# CoProcessor.net
KiCad netlist of a schematic drawn in Altium Designer
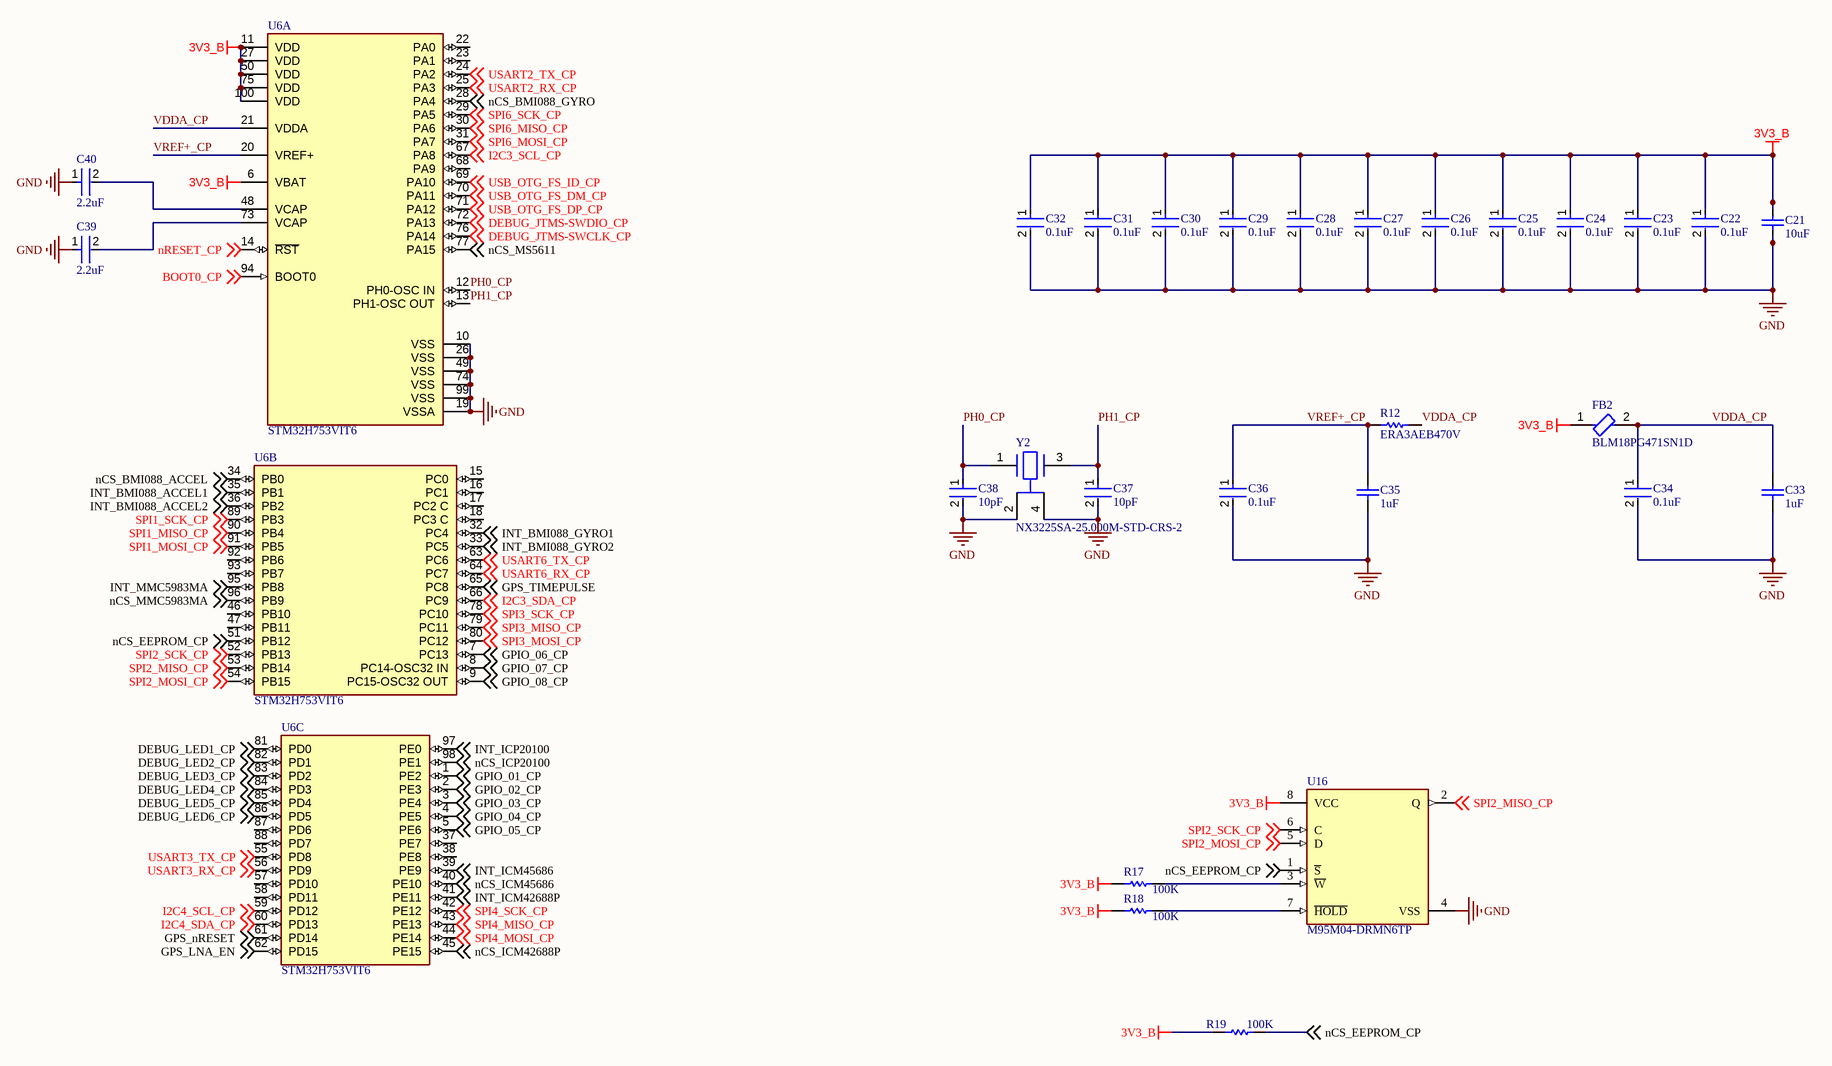
[diagram p0: CoProcessor.SchDoc]

(export (version "E")
  (design (tool "Eeschema 10.0.6"))
  (components
    (comp (ref "C21")
      (value "10uF")
      (footprint "CAPC2013X145X50LL20T25")
      (fields (field (name "MANUFACTURER") "Kemet") (field (name "PART NUMBER") "C0805C106K8RACTU"))
      (libsource (lib "Altium Content Vault") (part "CAP"))
    )
    (comp (ref "C22")
      (value "0.1uF")
      (footprint "FP-C0603C-CF-MFG")
      (description "CAP CER 0.1UF 50V X7R 0603")
      (fields (field (name "TOLERANCE") "0.1") (field (name "MANUFACTURER") "KEMET"))
      (libsource (lib "Altium Content Vault") (part "b4654b650e69147ec39a6b967a45e02"))
    )
    (comp (ref "C23")
      (value "0.1uF")
      (footprint "FP-C0603C-CF-MFG")
      (description "CAP CER 0.1UF 50V X7R 0603")
      (fields (field (name "TOLERANCE") "0.1") (field (name "MANUFACTURER") "KEMET"))
      (libsource (lib "Altium Content Vault") (part "b4654b650e69147ec39a6b967a45e02"))
    )
    (comp (ref "C24")
      (value "0.1uF")
      (footprint "FP-C0603C-CF-MFG")
      (description "CAP CER 0.1UF 50V X7R 0603")
      (fields (field (name "TOLERANCE") "0.1") (field (name "MANUFACTURER") "KEMET"))
      (libsource (lib "Altium Content Vault") (part "b4654b650e69147ec39a6b967a45e02"))
    )
    (comp (ref "C25")
      (value "0.1uF")
      (footprint "FP-C0603C-CF-MFG")
      (description "CAP CER 0.1UF 50V X7R 0603")
      (fields (field (name "TOLERANCE") "0.1") (field (name "MANUFACTURER") "KEMET"))
      (libsource (lib "Altium Content Vault") (part "b4654b650e69147ec39a6b967a45e02"))
    )
    (comp (ref "C26")
      (value "0.1uF")
      (footprint "FP-C0603C-CF-MFG")
      (description "CAP CER 0.1UF 50V X7R 0603")
      (fields (field (name "TOLERANCE") "0.1") (field (name "MANUFACTURER") "KEMET"))
      (libsource (lib "Altium Content Vault") (part "b4654b650e69147ec39a6b967a45e02"))
    )
    (comp (ref "C27")
      (value "0.1uF")
      (footprint "FP-C0603C-CF-MFG")
      (description "CAP CER 0.1UF 50V X7R 0603")
      (fields (field (name "TOLERANCE") "0.1") (field (name "MANUFACTURER") "KEMET"))
      (libsource (lib "Altium Content Vault") (part "b4654b650e69147ec39a6b967a45e02"))
    )
    (comp (ref "C28")
      (value "0.1uF")
      (footprint "FP-C0603C-CF-MFG")
      (description "CAP CER 0.1UF 50V X7R 0603")
      (fields (field (name "TOLERANCE") "0.1") (field (name "MANUFACTURER") "KEMET"))
      (libsource (lib "Altium Content Vault") (part "b4654b650e69147ec39a6b967a45e02"))
    )
    (comp (ref "C29")
      (value "0.1uF")
      (footprint "FP-C0603C-CF-MFG")
      (description "CAP CER 0.1UF 50V X7R 0603")
      (fields (field (name "TOLERANCE") "0.1") (field (name "MANUFACTURER") "KEMET"))
      (libsource (lib "Altium Content Vault") (part "b4654b650e69147ec39a6b967a45e02"))
    )
    (comp (ref "C30")
      (value "0.1uF")
      (footprint "FP-C0603C-CF-MFG")
      (description "CAP CER 0.1UF 50V X7R 0603")
      (fields (field (name "TOLERANCE") "0.1") (field (name "MANUFACTURER") "KEMET"))
      (libsource (lib "Altium Content Vault") (part "b4654b650e69147ec39a6b967a45e02"))
    )
    (comp (ref "C31")
      (value "0.1uF")
      (footprint "FP-C0603C-CF-MFG")
      (description "CAP CER 0.1UF 50V X7R 0603")
      (fields (field (name "TOLERANCE") "0.1") (field (name "MANUFACTURER") "KEMET"))
      (libsource (lib "Altium Content Vault") (part "b4654b650e69147ec39a6b967a45e02"))
    )
    (comp (ref "C32")
      (value "0.1uF")
      (footprint "FP-C0603C-CF-MFG")
      (description "CAP CER 0.1UF 50V X7R 0603")
      (fields (field (name "TOLERANCE") "0.1") (field (name "MANUFACTURER") "KEMET"))
      (libsource (lib "Altium Content Vault") (part "b4654b650e69147ec39a6b967a45e02"))
    )
    (comp (ref "C33")
      (value "1uF")
      (footprint "CAPC1608X90X35LL15T15")
      (fields (field (name "MANUFACTURER") "Kemet") (field (name "PART NUMBER") "C0603C105K4RACTU"))
      (libsource (lib "Altium Content Vault") (part "CAP"))
    )
    (comp (ref "C34")
      (value "0.1uF")
      (footprint "FP-C0603C-CF-MFG")
      (description "CAP CER 0.1UF 50V X7R 0603")
      (fields (field (name "TOLERANCE") "0.1") (field (name "MANUFACTURER") "KEMET"))
      (libsource (lib "Altium Content Vault") (part "b4654b650e69147ec39a6b967a45e02"))
    )
    (comp (ref "C35")
      (value "1uF")
      (footprint "CAPC1608X90X35LL15T15")
      (fields (field (name "MANUFACTURER") "Kemet") (field (name "PART NUMBER") "C0603C105K4RACTU"))
      (libsource (lib "Altium Content Vault") (part "CAP"))
    )
    (comp (ref "C36")
      (value "0.1uF")
      (footprint "FP-C0603C-CF-MFG")
      (description "CAP CER 0.1UF 50V X7R 0603")
      (fields (field (name "TOLERANCE") "0.1") (field (name "MANUFACTURER") "KEMET"))
      (libsource (lib "Altium Content Vault") (part "b4654b650e69147ec39a6b967a45e02"))
    )
    (comp (ref "C37")
      (value "10pF")
      (footprint "FP-C0603C-CF-MFG")
      (description "CAP CER 10PF 50V NP0 0603")
      (fields (field (name "MANUFACTURER") "KEMET") (field (name "TOLERANCE") "0.25 pF"))
      (libsource (lib "Altium Content Vault") (part "b4654b650e69147ec39a6b967a45e02"))
    )
    (comp (ref "C38")
      (value "10pF")
      (footprint "FP-C0603C-CF-MFG")
      (description "CAP CER 10PF 50V NP0 0603")
      (fields (field (name "MANUFACTURER") "KEMET") (field (name "TOLERANCE") "0.25 pF"))
      (libsource (lib "Altium Content Vault") (part "b4654b650e69147ec39a6b967a45e02"))
    )
    (comp (ref "C39")
      (value "2.2uF")
      (footprint "FP-GRM188-0_1-e0_2_0_5-MFG")
      (description "Chip Multilayer Ceramic Capacitors for General Purpose, 0603, 2.2uF, X7R, 15%, 10%, 10V")
      (fields (field (name "VOLTAGE") "10V") (field (name "TOLERANCE") "10%"))
      (libsource (lib "Altium Content Vault") (part "11868f565c42a9108669ba33697ecf6"))
    )
    (comp (ref "C40")
      (value "2.2uF")
      (footprint "FP-GRM188-0_1-e0_2_0_5-MFG")
      (description "Chip Multilayer Ceramic Capacitors for General Purpose, 0603, 2.2uF, X7R, 15%, 10%, 10V")
      (fields (field (name "VOLTAGE") "10V") (field (name "TOLERANCE") "10%"))
      (libsource (lib "Altium Content Vault") (part "11868f565c42a9108669ba33697ecf6"))
    )
    (comp (ref "FB2")
      (value "BLM18PG471SN1D")
      (footprint "FP-BLM18-0_15-t0_8-MFG")
      (description "Chip Ferrite Bead, 0603, 470Ω @ 100MHz, 0.2Ω, 25%, 1A")
      (fields (field (name "TOLERANCE") "25%"))
      (libsource (lib "Altium Content Vault") (part "5f30dd21d616792df468990f7003faa"))
    )
    (comp (ref "R12")
      (value "ERA3AEB470V")
      (footprint "RESC1608X55X30NL20T20")
      (fields (field (name "MANUFACTURER") "Panasonic"))
      (libsource (lib "Altium Content Vault") (part "RES"))
    )
    (comp (ref "R17")
      (value "100K")
      (footprint "RESC1608X55X30ML20T10")
      (fields (field (name "PART NUMBER") "RK73B1JTTD104J") (field (name "MANUFACTURER") "KOA Speer"))
      (libsource (lib "Altium Content Vault") (part "RES"))
    )
    (comp (ref "R18")
      (value "100K")
      (footprint "RESC1608X55X30ML20T10")
      (fields (field (name "PART NUMBER") "RK73B1JTTD104J") (field (name "MANUFACTURER") "KOA Speer"))
      (libsource (lib "Altium Content Vault") (part "RES"))
    )
    (comp (ref "R19")
      (value "100K")
      (footprint "RESC1608X55X30ML20T10")
      (fields (field (name "PART NUMBER") "RK73B1JTTD104J") (field (name "MANUFACTURER") "KOA Speer"))
      (libsource (lib "Altium Content Vault") (part "RES"))
    )
    (comp (ref "U6")
      (value "STM32H753VIT6")
      (footprint "FP-LQFP100-1L-MFG")
      (description "LQFP 100 14X14X1.4")
      (fields
        (field (name "OCTOPART") "https://octopart.com/stm32h753vit6-stmicroelectronics-87879769")
        (field (name "MANUFACTURER") "STMicroelectronics")
      )
      (libsource (lib "Altium Content Vault") (part "0d804454ec25a714beb1806164230ed"))
    )
    (comp (ref "U16")
      (value "M95M04-DRMN6TP")
      (footprint "FP-SO8N-SO-A-IPC_C")
      (description "STANDARD SERIAL EEPROM")
      (libsource (lib "Altium Content Vault") (part "c55af301368cfa6937ebbf8cb00c05d"))
    )
    (comp (ref "Y2")
      (value "NX3225SA-25.000M-STD-CRS-2")
      (footprint "FP-NX3225SA-MFG")
      (description "CRYSTAL 25.0000MHZ 8PF SMD")
      (fields
        (field (name "OCTOPART") "https://octopart.com/nx3225sa-25.000m-std-crs-2-ndk-51374293")
        (field (name "MANUFACTURER") "NDK")
      )
      (libsource (lib "Altium Content Vault") (part "2e6e5a9c86ccbddb5e6335a7c0ff6ff"))
    )
  )
  (nets
    (net (code "1") (name "/PH0_CP") (class "Default")
      (node (ref "C38") (pin "1") (pinfunction "1_1") (pintype "passive"))
      (node (ref "U6") (pin "12") (pinfunction "PH0-OSC_IN_12") (pintype "bidirectional"))
      (node (ref "Y2") (pin "1") (pinfunction "1_1") (pintype "passive"))
    )
    (net (code "2") (name "/PH1_CP") (class "Default")
      (node (ref "C37") (pin "1") (pinfunction "1_1") (pintype "passive"))
      (node (ref "U6") (pin "13") (pinfunction "PH1-OSC_OUT_13") (pintype "bidirectional"))
      (node (ref "Y2") (pin "3") (pinfunction "3_3") (pintype "passive"))
    )
    (net (code "3") (name "/VDDA_CP") (class "Default")
      (node (ref "C33") (pin "1") (pinfunction "1_1") (pintype "passive"))
      (node (ref "C34") (pin "1") (pinfunction "1_1") (pintype "passive"))
      (node (ref "FB2") (pin "2") (pinfunction "2_2") (pintype "passive"))
      (node (ref "R12") (pin "2") (pinfunction "2_2") (pintype "passive"))
      (node (ref "U6") (pin "21") (pinfunction "VDDA_21") (pintype "power_in"))
    )
    (net (code "4") (name "/VREF+_CP") (class "Default")
      (node (ref "C35") (pin "1") (pinfunction "1_1") (pintype "passive"))
      (node (ref "C36") (pin "1") (pinfunction "1_1") (pintype "passive"))
      (node (ref "R12") (pin "1") (pinfunction "1_1") (pintype "passive"))
      (node (ref "U6") (pin "20") (pinfunction "VREF+_20") (pintype "power_in"))
    )
    (net (code "5") (name "3V3_B") (class "Default")
      (node (ref "C21") (pin "1") (pinfunction "1_1") (pintype "passive"))
      (node (ref "C22") (pin "1") (pinfunction "1_1") (pintype "passive"))
      (node (ref "C23") (pin "1") (pinfunction "1_1") (pintype "passive"))
      (node (ref "C24") (pin "1") (pinfunction "1_1") (pintype "passive"))
      (node (ref "C25") (pin "1") (pinfunction "1_1") (pintype "passive"))
      (node (ref "C26") (pin "1") (pinfunction "1_1") (pintype "passive"))
      (node (ref "C27") (pin "1") (pinfunction "1_1") (pintype "passive"))
      (node (ref "C28") (pin "1") (pinfunction "1_1") (pintype "passive"))
      (node (ref "C29") (pin "1") (pinfunction "1_1") (pintype "passive"))
      (node (ref "C30") (pin "1") (pinfunction "1_1") (pintype "passive"))
      (node (ref "C31") (pin "1") (pinfunction "1_1") (pintype "passive"))
      (node (ref "C32") (pin "1") (pinfunction "1_1") (pintype "passive"))
      (node (ref "FB2") (pin "1") (pinfunction "1_1") (pintype "passive"))
      (node (ref "R17") (pin "2") (pinfunction "2_2") (pintype "passive"))
      (node (ref "R18") (pin "2") (pinfunction "2_2") (pintype "passive"))
      (node (ref "R19") (pin "2") (pinfunction "2_2") (pintype "passive"))
      (node (ref "U16") (pin "8") (pinfunction "VCC_8") (pintype "power_in"))
      (node (ref "U6") (pin "100") (pinfunction "VDD_100") (pintype "power_in"))
      (node (ref "U6") (pin "11") (pinfunction "VDD_11") (pintype "power_in"))
      (node (ref "U6") (pin "27") (pinfunction "VDD_27") (pintype "power_in"))
      (node (ref "U6") (pin "50") (pinfunction "VDD_50") (pintype "power_in"))
      (node (ref "U6") (pin "6") (pinfunction "VBAT_6") (pintype "power_in"))
      (node (ref "U6") (pin "75") (pinfunction "VDD_75") (pintype "power_in"))
    )
    (net (code "6") (name "BOOT0_CP") (class "Default")
      (node (ref "U6") (pin "94") (pinfunction "BOOT0_94") (pintype "input"))
    )
    (net (code "7") (name "DEBUG_JTMS-SWCLK_CP") (class "Default")
      (node (ref "U6") (pin "76") (pinfunction "PA14_76") (pintype "bidirectional"))
    )
    (net (code "8") (name "DEBUG_JTMS-SWDIO_CP") (class "Default")
      (node (ref "U6") (pin "72") (pinfunction "PA13_72") (pintype "bidirectional"))
    )
    (net (code "9") (name "DEBUG_LED1_CP") (class "Default")
      (node (ref "U6") (pin "81") (pinfunction "PD0_81") (pintype "bidirectional"))
    )
    (net (code "10") (name "DEBUG_LED2_CP") (class "Default")
      (node (ref "U6") (pin "82") (pinfunction "PD1_82") (pintype "bidirectional"))
    )
    (net (code "11") (name "DEBUG_LED3_CP") (class "Default")
      (node (ref "U6") (pin "83") (pinfunction "PD2_83") (pintype "bidirectional"))
    )
    (net (code "12") (name "DEBUG_LED4_CP") (class "Default")
      (node (ref "U6") (pin "84") (pinfunction "PD3_84") (pintype "bidirectional"))
    )
    (net (code "13") (name "DEBUG_LED5_CP") (class "Default")
      (node (ref "U6") (pin "85") (pinfunction "PD4_85") (pintype "bidirectional"))
    )
    (net (code "14") (name "DEBUG_LED6_CP") (class "Default")
      (node (ref "U6") (pin "86") (pinfunction "PD5_86") (pintype "bidirectional"))
    )
    (net (code "15") (name "GND") (class "Default")
      (node (ref "C21") (pin "2") (pinfunction "2_2") (pintype "passive"))
      (node (ref "C22") (pin "2") (pinfunction "2_2") (pintype "passive"))
      (node (ref "C23") (pin "2") (pinfunction "2_2") (pintype "passive"))
      (node (ref "C24") (pin "2") (pinfunction "2_2") (pintype "passive"))
      (node (ref "C25") (pin "2") (pinfunction "2_2") (pintype "passive"))
      (node (ref "C26") (pin "2") (pinfunction "2_2") (pintype "passive"))
      (node (ref "C27") (pin "2") (pinfunction "2_2") (pintype "passive"))
      (node (ref "C28") (pin "2") (pinfunction "2_2") (pintype "passive"))
      (node (ref "C29") (pin "2") (pinfunction "2_2") (pintype "passive"))
      (node (ref "C30") (pin "2") (pinfunction "2_2") (pintype "passive"))
      (node (ref "C31") (pin "2") (pinfunction "2_2") (pintype "passive"))
      (node (ref "C32") (pin "2") (pinfunction "2_2") (pintype "passive"))
      (node (ref "C33") (pin "2") (pinfunction "2_2") (pintype "passive"))
      (node (ref "C34") (pin "2") (pinfunction "2_2") (pintype "passive"))
      (node (ref "C35") (pin "2") (pinfunction "2_2") (pintype "passive"))
      (node (ref "C36") (pin "2") (pinfunction "2_2") (pintype "passive"))
      (node (ref "C37") (pin "2") (pinfunction "2_2") (pintype "passive"))
      (node (ref "C38") (pin "2") (pinfunction "2_2") (pintype "passive"))
      (node (ref "C39") (pin "1") (pinfunction "1_1") (pintype "passive"))
      (node (ref "C40") (pin "1") (pinfunction "1_1") (pintype "passive"))
      (node (ref "U16") (pin "4") (pinfunction "VSS_4") (pintype "power_in"))
      (node (ref "U6") (pin "10") (pinfunction "VSS_10") (pintype "power_in"))
      (node (ref "U6") (pin "19") (pinfunction "VSSA_19") (pintype "power_in"))
      (node (ref "U6") (pin "26") (pinfunction "VSS_26") (pintype "power_in"))
      (node (ref "U6") (pin "49") (pinfunction "VSS_49") (pintype "power_in"))
      (node (ref "U6") (pin "74") (pinfunction "VSS_74") (pintype "power_in"))
      (node (ref "U6") (pin "99") (pinfunction "VSS_99") (pintype "power_in"))
      (node (ref "Y2") (pin "2") (pinfunction "GND_2") (pintype "power_in"))
      (node (ref "Y2") (pin "4") (pinfunction "GND_4") (pintype "power_in"))
    )
    (net (code "16") (name "GPIO_01_CP") (class "Default")
      (node (ref "U6") (pin "1") (pinfunction "PE2_1") (pintype "bidirectional"))
    )
    (net (code "17") (name "GPIO_02_CP") (class "Default")
      (node (ref "U6") (pin "2") (pinfunction "PE3_2") (pintype "bidirectional"))
    )
    (net (code "18") (name "GPIO_03_CP") (class "Default")
      (node (ref "U6") (pin "3") (pinfunction "PE4_3") (pintype "bidirectional"))
    )
    (net (code "19") (name "GPIO_04_CP") (class "Default")
      (node (ref "U6") (pin "4") (pinfunction "PE5_4") (pintype "bidirectional"))
    )
    (net (code "20") (name "GPIO_05_CP") (class "Default")
      (node (ref "U6") (pin "5") (pinfunction "PE6_5") (pintype "bidirectional"))
    )
    (net (code "21") (name "GPIO_06_CP") (class "Default")
      (node (ref "U6") (pin "7") (pinfunction "PC13_7") (pintype "bidirectional"))
    )
    (net (code "22") (name "GPIO_07_CP") (class "Default")
      (node (ref "U6") (pin "8") (pinfunction "PC14-OSC32_IN_8") (pintype "bidirectional"))
    )
    (net (code "23") (name "GPIO_08_CP") (class "Default")
      (node (ref "U6") (pin "9") (pinfunction "PC15-OSC32_OUT_9") (pintype "bidirectional"))
    )
    (net (code "24") (name "GPS_LNA_EN") (class "Default")
      (node (ref "U6") (pin "62") (pinfunction "PD15_62") (pintype "bidirectional"))
    )
    (net (code "25") (name "GPS_TIMEPULSE") (class "Default")
      (node (ref "U6") (pin "65") (pinfunction "PC8_65") (pintype "bidirectional"))
    )
    (net (code "26") (name "GPS_nRESET") (class "Default")
      (node (ref "U6") (pin "61") (pinfunction "PD14_61") (pintype "bidirectional"))
    )
    (net (code "27") (name "I2C3_SCL_CP") (class "Default")
      (node (ref "U6") (pin "67") (pinfunction "PA8_67") (pintype "bidirectional"))
    )
    (net (code "28") (name "I2C3_SDA_CP") (class "Default")
      (node (ref "U6") (pin "66") (pinfunction "PC9_66") (pintype "bidirectional"))
    )
    (net (code "29") (name "I2C4_SCL_CP") (class "Default")
      (node (ref "U6") (pin "59") (pinfunction "PD12_59") (pintype "bidirectional"))
    )
    (net (code "30") (name "I2C4_SDA_CP") (class "Default")
      (node (ref "U6") (pin "60") (pinfunction "PD13_60") (pintype "bidirectional"))
    )
    (net (code "31") (name "INT_BMI088_ACCEL1") (class "Default")
      (node (ref "U6") (pin "35") (pinfunction "PB1_35") (pintype "bidirectional"))
    )
    (net (code "32") (name "INT_BMI088_ACCEL2") (class "Default")
      (node (ref "U6") (pin "36") (pinfunction "PB2_36") (pintype "bidirectional"))
    )
    (net (code "33") (name "INT_BMI088_GYRO1") (class "Default")
      (node (ref "U6") (pin "32") (pinfunction "PC4_32") (pintype "bidirectional"))
    )
    (net (code "34") (name "INT_BMI088_GYRO2") (class "Default")
      (node (ref "U6") (pin "33") (pinfunction "PC5_33") (pintype "bidirectional"))
    )
    (net (code "35") (name "INT_ICM42688P") (class "Default")
      (node (ref "U6") (pin "41") (pinfunction "PE11_41") (pintype "bidirectional"))
    )
    (net (code "36") (name "INT_ICM45686") (class "Default")
      (node (ref "U6") (pin "39") (pinfunction "PE9_39") (pintype "bidirectional"))
    )
    (net (code "37") (name "INT_ICP20100") (class "Default")
      (node (ref "U6") (pin "97") (pinfunction "PE0_97") (pintype "bidirectional"))
    )
    (net (code "38") (name "INT_MMC5983MA") (class "Default")
      (node (ref "U6") (pin "95") (pinfunction "PB8_95") (pintype "bidirectional"))
    )
    (net (code "39") (name "Net-(C39-Pad2)") (class "Default")
      (node (ref "C39") (pin "2") (pinfunction "2_2") (pintype "passive"))
      (node (ref "U6") (pin "73") (pinfunction "VCAP_73") (pintype "power_in"))
    )
    (net (code "40") (name "Net-(C40-Pad2)") (class "Default")
      (node (ref "C40") (pin "2") (pinfunction "2_2") (pintype "passive"))
      (node (ref "U6") (pin "48") (pinfunction "VCAP_48") (pintype "power_in"))
    )
    (net (code "41") (name "Net-(U16-~{HOLD})") (class "Default")
      (node (ref "R18") (pin "1") (pinfunction "1_1") (pintype "passive"))
      (node (ref "U16") (pin "7") (pinfunction "~{HOLD}_7") (pintype "input"))
    )
    (net (code "42") (name "Net-(U16-~{W})") (class "Default")
      (node (ref "R17") (pin "1") (pinfunction "1_1") (pintype "passive"))
      (node (ref "U16") (pin "3") (pinfunction "~{W}_3") (pintype "input"))
    )
    (net (code "43") (name "SPI1_MISO_CP") (class "Default")
      (node (ref "U6") (pin "90") (pinfunction "PB4_90") (pintype "bidirectional"))
    )
    (net (code "44") (name "SPI1_MOSI_CP") (class "Default")
      (node (ref "U6") (pin "91") (pinfunction "PB5_91") (pintype "bidirectional"))
    )
    (net (code "45") (name "SPI1_SCK_CP") (class "Default")
      (node (ref "U6") (pin "89") (pinfunction "PB3_89") (pintype "bidirectional"))
    )
    (net (code "46") (name "SPI2_MISO_CP") (class "Default")
      (node (ref "U16") (pin "2") (pinfunction "Q_2") (pintype "output"))
      (node (ref "U6") (pin "53") (pinfunction "PB14_53") (pintype "bidirectional"))
    )
    (net (code "47") (name "SPI2_MOSI_CP") (class "Default")
      (node (ref "U16") (pin "5") (pinfunction "D_5") (pintype "input"))
      (node (ref "U6") (pin "54") (pinfunction "PB15_54") (pintype "bidirectional"))
    )
    (net (code "48") (name "SPI2_SCK_CP") (class "Default")
      (node (ref "U16") (pin "6") (pinfunction "C_6") (pintype "input"))
      (node (ref "U6") (pin "52") (pinfunction "PB13_52") (pintype "bidirectional"))
    )
    (net (code "49") (name "SPI3_MISO_CP") (class "Default")
      (node (ref "U6") (pin "79") (pinfunction "PC11_79") (pintype "bidirectional"))
    )
    (net (code "50") (name "SPI3_MOSI_CP") (class "Default")
      (node (ref "U6") (pin "80") (pinfunction "PC12_80") (pintype "bidirectional"))
    )
    (net (code "51") (name "SPI3_SCK_CP") (class "Default")
      (node (ref "U6") (pin "78") (pinfunction "PC10_78") (pintype "bidirectional"))
    )
    (net (code "52") (name "SPI4_MISO_CP") (class "Default")
      (node (ref "U6") (pin "43") (pinfunction "PE13_43") (pintype "bidirectional"))
    )
    (net (code "53") (name "SPI4_MOSI_CP") (class "Default")
      (node (ref "U6") (pin "44") (pinfunction "PE14_44") (pintype "bidirectional"))
    )
    (net (code "54") (name "SPI4_SCK_CP") (class "Default")
      (node (ref "U6") (pin "42") (pinfunction "PE12_42") (pintype "bidirectional"))
    )
    (net (code "55") (name "SPI6_MISO_CP") (class "Default")
      (node (ref "U6") (pin "30") (pinfunction "PA6_30") (pintype "bidirectional"))
    )
    (net (code "56") (name "SPI6_MOSI_CP") (class "Default")
      (node (ref "U6") (pin "31") (pinfunction "PA7_31") (pintype "bidirectional"))
    )
    (net (code "57") (name "SPI6_SCK_CP") (class "Default")
      (node (ref "U6") (pin "29") (pinfunction "PA5_29") (pintype "bidirectional"))
    )
    (net (code "58") (name "USART2_RX_CP") (class "Default")
      (node (ref "U6") (pin "25") (pinfunction "PA3_25") (pintype "bidirectional"))
    )
    (net (code "59") (name "USART2_TX_CP") (class "Default")
      (node (ref "U6") (pin "24") (pinfunction "PA2_24") (pintype "bidirectional"))
    )
    (net (code "60") (name "USART3_RX_CP") (class "Default")
      (node (ref "U6") (pin "56") (pinfunction "PD9_56") (pintype "bidirectional"))
    )
    (net (code "61") (name "USART3_TX_CP") (class "Default")
      (node (ref "U6") (pin "55") (pinfunction "PD8_55") (pintype "bidirectional"))
    )
    (net (code "62") (name "USART6_RX_CP") (class "Default")
      (node (ref "U6") (pin "64") (pinfunction "PC7_64") (pintype "bidirectional"))
    )
    (net (code "63") (name "USART6_TX_CP") (class "Default")
      (node (ref "U6") (pin "63") (pinfunction "PC6_63") (pintype "bidirectional"))
    )
    (net (code "64") (name "USB_OTG_FS_DM_CP") (class "Default")
      (node (ref "U6") (pin "70") (pinfunction "PA11_70") (pintype "bidirectional"))
    )
    (net (code "65") (name "USB_OTG_FS_DP_CP") (class "Default")
      (node (ref "U6") (pin "71") (pinfunction "PA12_71") (pintype "bidirectional"))
    )
    (net (code "66") (name "USB_OTG_FS_ID_CP") (class "Default")
      (node (ref "U6") (pin "69") (pinfunction "PA10_69") (pintype "bidirectional"))
    )
    (net (code "67") (name "nCS_BMI088_ACCEL") (class "Default")
      (node (ref "U6") (pin "34") (pinfunction "PB0_34") (pintype "bidirectional"))
    )
    (net (code "68") (name "nCS_BMI088_GYRO") (class "Default")
      (node (ref "U6") (pin "28") (pinfunction "PA4_28") (pintype "bidirectional"))
    )
    (net (code "69") (name "nCS_EEPROM_CP") (class "Default")
      (node (ref "R19") (pin "1") (pinfunction "1_1") (pintype "passive"))
      (node (ref "U16") (pin "1") (pinfunction "~{S}_1") (pintype "input"))
      (node (ref "U6") (pin "51") (pinfunction "PB12_51") (pintype "bidirectional"))
    )
    (net (code "70") (name "nCS_ICM42688P") (class "Default")
      (node (ref "U6") (pin "45") (pinfunction "PE15_45") (pintype "bidirectional"))
    )
    (net (code "71") (name "nCS_ICM45686") (class "Default")
      (node (ref "U6") (pin "40") (pinfunction "PE10_40") (pintype "bidirectional"))
    )
    (net (code "72") (name "nCS_ICP20100") (class "Default")
      (node (ref "U6") (pin "98") (pinfunction "PE1_98") (pintype "bidirectional"))
    )
    (net (code "73") (name "nCS_MMC5983MA") (class "Default")
      (node (ref "U6") (pin "96") (pinfunction "PB9_96") (pintype "bidirectional"))
    )
    (net (code "74") (name "nCS_MS5611") (class "Default")
      (node (ref "U6") (pin "77") (pinfunction "PA15_77") (pintype "bidirectional"))
    )
    (net (code "75") (name "nRESET_CP") (class "Default")
      (node (ref "U6") (pin "14") (pinfunction "~{RST}_14") (pintype "bidirectional"))
    )
    (net (code "76") (name "unconnected-(U6A-PA0-Pad22)") (class "Default")
      (node (ref "U6") (pin "22") (pinfunction "PA0_22") (pintype "bidirectional"))
    )
    (net (code "77") (name "unconnected-(U6A-PA1-Pad23)") (class "Default")
      (node (ref "U6") (pin "23") (pinfunction "PA1_23") (pintype "bidirectional"))
    )
    (net (code "78") (name "unconnected-(U6A-PA9-Pad68)") (class "Default")
      (node (ref "U6") (pin "68") (pinfunction "PA9_68") (pintype "bidirectional"))
    )
    (net (code "79") (name "unconnected-(U6B-PB6-Pad92)") (class "Default")
      (node (ref "U6") (pin "92") (pinfunction "PB6_92") (pintype "bidirectional"))
    )
    (net (code "80") (name "unconnected-(U6B-PB7-Pad93)") (class "Default")
      (node (ref "U6") (pin "93") (pinfunction "PB7_93") (pintype "bidirectional"))
    )
    (net (code "81") (name "unconnected-(U6B-PB10-Pad46)") (class "Default")
      (node (ref "U6") (pin "46") (pinfunction "PB10_46") (pintype "bidirectional"))
    )
    (net (code "82") (name "unconnected-(U6B-PB11-Pad47)") (class "Default")
      (node (ref "U6") (pin "47") (pinfunction "PB11_47") (pintype "bidirectional"))
    )
    (net (code "83") (name "unconnected-(U6B-PC0-Pad15)") (class "Default")
      (node (ref "U6") (pin "15") (pinfunction "PC0_15") (pintype "bidirectional"))
    )
    (net (code "84") (name "unconnected-(U6B-PC1-Pad16)") (class "Default")
      (node (ref "U6") (pin "16") (pinfunction "PC1_16") (pintype "bidirectional"))
    )
    (net (code "85") (name "unconnected-(U6B-PC2_C-Pad17)") (class "Default")
      (node (ref "U6") (pin "17") (pinfunction "PC2_C_17") (pintype "bidirectional"))
    )
    (net (code "86") (name "unconnected-(U6B-PC3_C-Pad18)") (class "Default")
      (node (ref "U6") (pin "18") (pinfunction "PC3_C_18") (pintype "bidirectional"))
    )
    (net (code "87") (name "unconnected-(U6C-PD6-Pad87)") (class "Default")
      (node (ref "U6") (pin "87") (pinfunction "PD6_87") (pintype "bidirectional"))
    )
    (net (code "88") (name "unconnected-(U6C-PD7-Pad88)") (class "Default")
      (node (ref "U6") (pin "88") (pinfunction "PD7_88") (pintype "bidirectional"))
    )
    (net (code "89") (name "unconnected-(U6C-PD10-Pad57)") (class "Default")
      (node (ref "U6") (pin "57") (pinfunction "PD10_57") (pintype "bidirectional"))
    )
    (net (code "90") (name "unconnected-(U6C-PD11-Pad58)") (class "Default")
      (node (ref "U6") (pin "58") (pinfunction "PD11_58") (pintype "bidirectional"))
    )
    (net (code "91") (name "unconnected-(U6C-PE7-Pad37)") (class "Default")
      (node (ref "U6") (pin "37") (pinfunction "PE7_37") (pintype "bidirectional"))
    )
    (net (code "92") (name "unconnected-(U6C-PE8-Pad38)") (class "Default")
      (node (ref "U6") (pin "38") (pinfunction "PE8_38") (pintype "bidirectional"))
    )
  )
)
